# top_dsn.net
KiCad netlist of a schematic drawn in Altium Designer
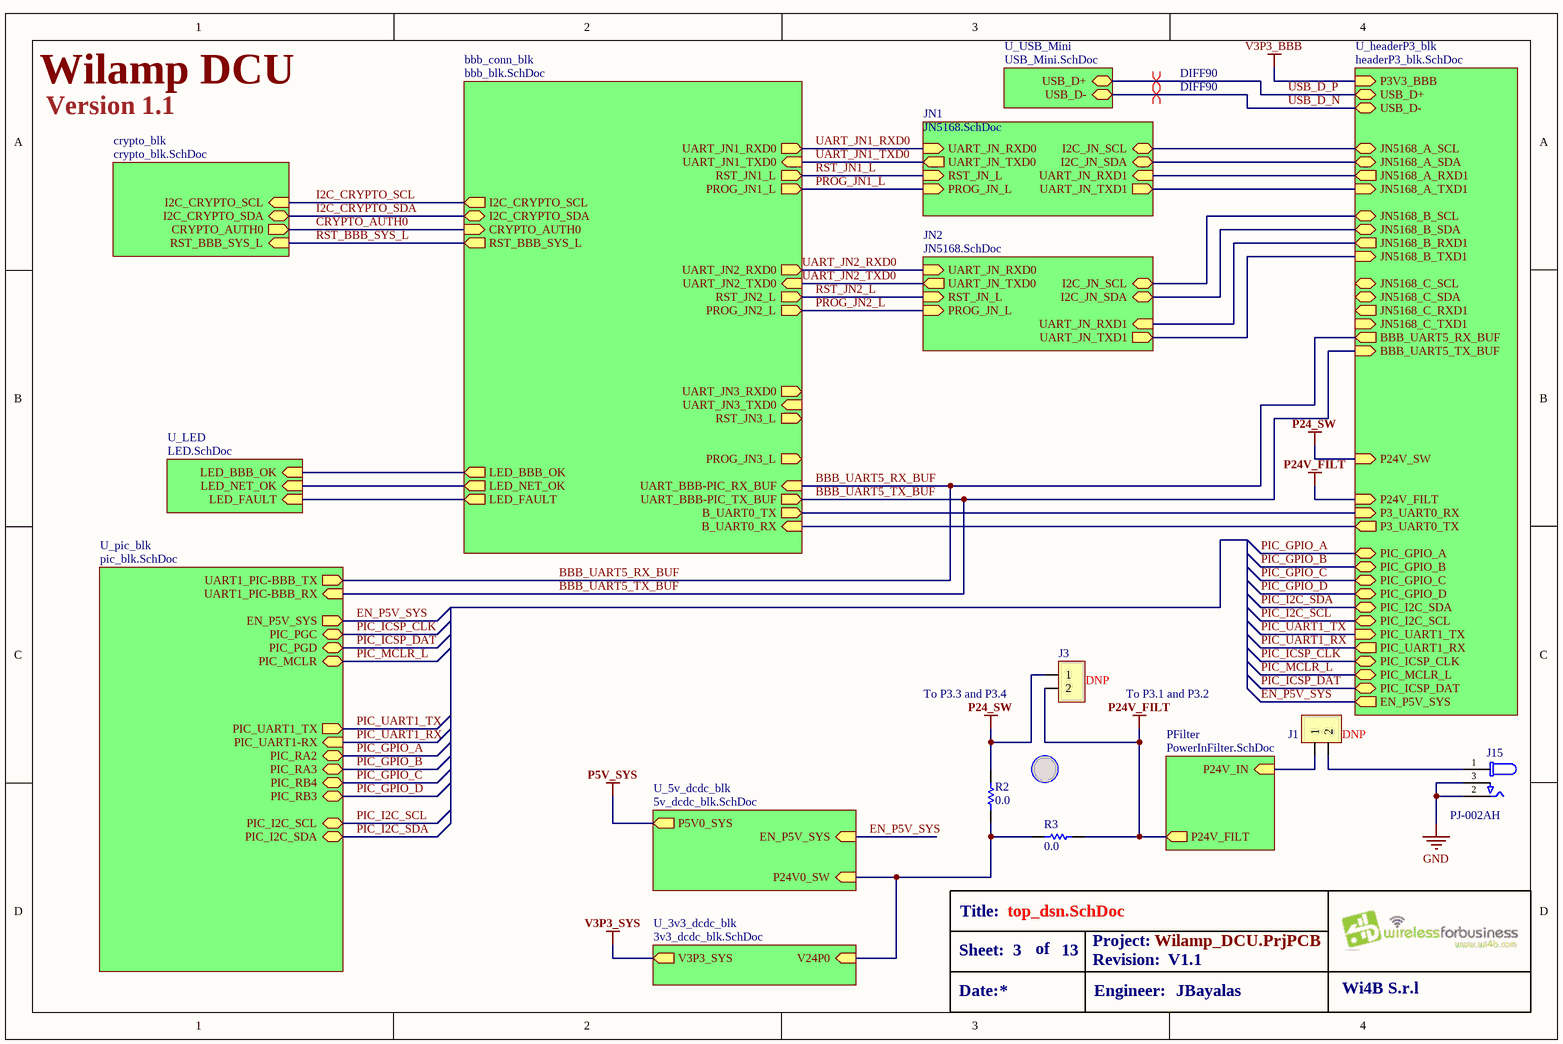
[diagram p0: top_dsn.SchDoc]

(export (version "E")
  (design (tool "Eeschema 10.0.6"))
  (components
    (comp (ref "J1")
      (value "*")
      (footprint "2pin 5mm Pitch")
      (fields (field (name "LOAD") "DNP"))
      (libsource (lib "") (part "2PIN Signal 5mm Pitch_1"))
    )
    (comp (ref "J3")
      (value "*")
      (footprint "2pin 5mm Pitch")
      (fields (field (name "LOAD") "DNP"))
      (libsource (lib "Miscellaneous") (part "2PIN Signal 5mm Pitch"))
    )
    (comp (ref "J15")
      (value "*")
      (footprint "PJ-002AH")
      (description "CONN PWR JACK 2.1X5.5MM HIGH CUR")
      (fields (field (name "MPN") "PJ-002AH"))
      (libsource (lib "Connector") (part "PJ-002AH"))
    )
    (comp (ref "R2")
      (value "0.0")
      (footprint "R0805")
      (description "RES SMD 0.0 OHM JUMPER 1/8W 0805")
      (fields (field (name "MPN") "RC0805JR-070RL"))
      (libsource (lib "Res") (part "RC0805JR-070RL"))
    )
    (comp (ref "R3")
      (value "0.0")
      (footprint "R0805")
      (description "RES SMD 0.0 OHM JUMPER 1/8W 0805")
      (fields (field (name "MPN") "RC0805JR-070RL"))
      (libsource (lib "Res") (part "RC0805JR-070RL"))
    )
  )
  (nets
    (net (code "22") (name "/P24V0_SW") (class "Default")
      (node (ref "R2") (pin "1") (pinfunction "1_1") (pintype "passive"))
      (node (ref "R3") (pin "1") (pinfunction "1_1") (pintype "passive"))
    )
    (net (code "23") (name "/P24V_IN") (class "Default")
      (node (ref "J1") (pin "1") (pinfunction "1_1") (pintype "passive"))
    )
    (net (code "52") (name "GND") (class "Default")
      (node (ref "J15") (pin "2") (pinfunction "2_2") (pintype "passive"))
      (node (ref "J15") (pin "3") (pinfunction "3_3") (pintype "passive"))
    )
    (net (code "53") (name "Net-(J1-Pad2)") (class "Default")
      (node (ref "J1") (pin "2") (pinfunction "2_2") (pintype "passive"))
      (node (ref "J15") (pin "1") (pinfunction "1_1") (pintype "passive"))
    )
    (net (code "55") (name "P24V_FILT") (class "Default")
      (node (ref "J3") (pin "2") (pinfunction "2_2") (pintype "passive"))
      (node (ref "R3") (pin "2") (pinfunction "2_2") (pintype "passive"))
    )
    (net (code "56") (name "P24_SW") (class "Default")
      (node (ref "J3") (pin "1") (pinfunction "1_1") (pintype "passive"))
      (node (ref "R2") (pin "2") (pinfunction "2_2") (pintype "passive"))
    )
  )
)
